# Windows_Hello_DIAL_HUB.net
KiCad netlist of a schematic drawn in EasyEDA Pro
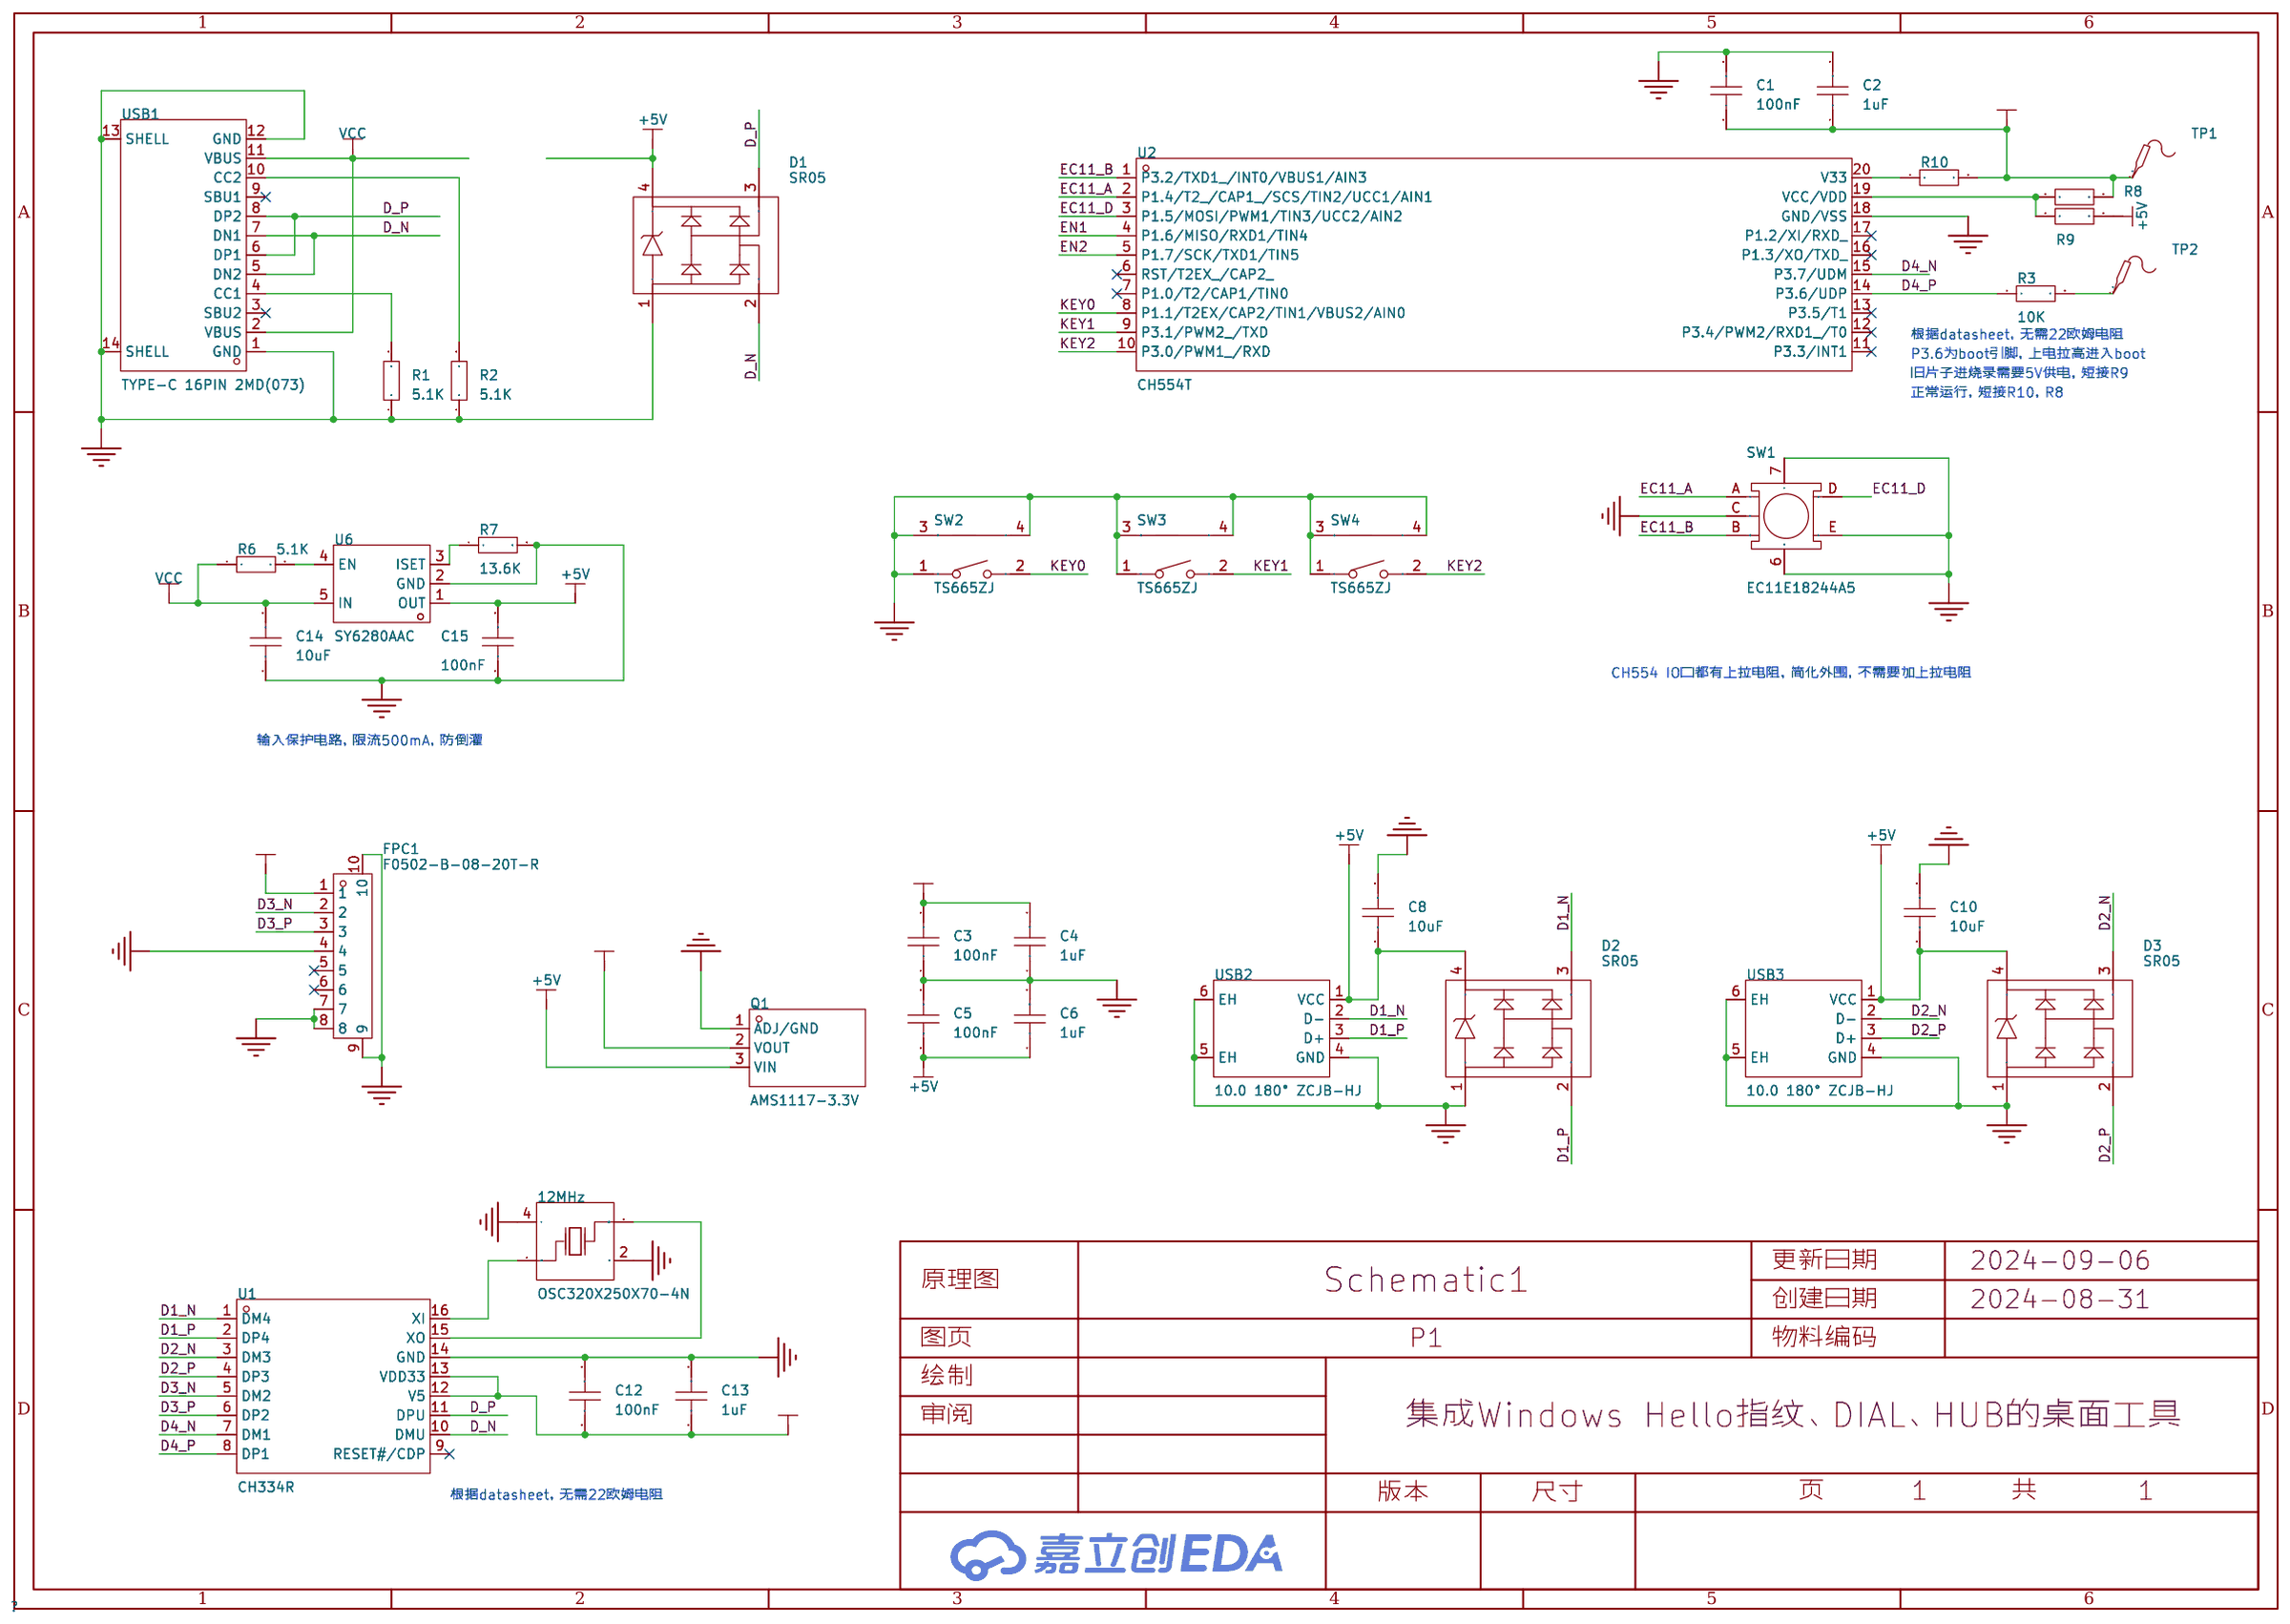
[diagram p0: schematic sheet]

(export (version "E")
  (design (tool "Eeschema 10.0.6"))
  (components
    (comp (ref "12MHz")
      (value "OSC320X250X70-4N")
      (footprint "easyedapro:CRYSTAL-SMD_4P-L3.2-W2.5-BL")
      (libsource (lib "easyedapro") (part "OSC320X250X70-4N"))
    )
    (comp (ref "C1")
      (value "100nF")
      (footprint "easyedapro:C0603")
      (libsource (lib "easyedapro") (part "CapAcitance"))
    )
    (comp (ref "C2")
      (value "1uF")
      (footprint "easyedapro:C0603")
      (libsource (lib "easyedapro") (part "CapAcitance"))
    )
    (comp (ref "C3")
      (value "100nF")
      (footprint "easyedapro:C0603")
      (libsource (lib "easyedapro") (part "CapAcitance"))
    )
    (comp (ref "C4")
      (value "1uF")
      (footprint "easyedapro:C0603")
      (libsource (lib "easyedapro") (part "CapAcitance"))
    )
    (comp (ref "C5")
      (value "100nF")
      (footprint "easyedapro:C0603")
      (libsource (lib "easyedapro") (part "CapAcitance"))
    )
    (comp (ref "C6")
      (value "1uF")
      (footprint "easyedapro:C0603")
      (libsource (lib "easyedapro") (part "CapAcitance"))
    )
    (comp (ref "C8")
      (value "10uF")
      (footprint "easyedapro:C0603")
      (libsource (lib "easyedapro") (part "CapAcitance"))
    )
    (comp (ref "C10")
      (value "10uF")
      (footprint "easyedapro:C0603")
      (libsource (lib "easyedapro") (part "CapAcitance"))
    )
    (comp (ref "C12")
      (value "100nF")
      (footprint "easyedapro:C0603")
      (libsource (lib "easyedapro") (part "CapAcitance"))
    )
    (comp (ref "C13")
      (value "1uF")
      (footprint "easyedapro:C0603")
      (libsource (lib "easyedapro") (part "CapAcitance"))
    )
    (comp (ref "C14")
      (value "10uF")
      (footprint "easyedapro:C0603")
      (libsource (lib "easyedapro") (part "CapAcitance"))
    )
    (comp (ref "C15")
      (value "100nF")
      (footprint "easyedapro:C0603")
      (libsource (lib "easyedapro") (part "CapAcitance"))
    )
    (comp (ref "D1")
      (value "SR05")
      (footprint "easyedapro:SOT-143-4_L2.9-W1.3-P1.90-LS2.4-BL")
      (fields (field (name "Manufacturer") "SEMBO(深波)"))
      (libsource (lib "easyedapro") (part "SR05_C782796"))
    )
    (comp (ref "D2")
      (value "SR05")
      (footprint "easyedapro:SOT-143-4_L2.9-W1.3-P1.90-LS2.4-BL")
      (fields (field (name "Manufacturer") "SEMBO(深波)"))
      (libsource (lib "easyedapro") (part "SR05_C782796"))
    )
    (comp (ref "D3")
      (value "SR05")
      (footprint "easyedapro:SOT-143-4_L2.9-W1.3-P1.90-LS2.4-BL")
      (fields (field (name "Manufacturer") "SEMBO(深波)"))
      (libsource (lib "easyedapro") (part "SR05_C782796"))
    )
    (comp (ref "FPC1")
      (value "F0502-B-08-20T-R")
      (footprint "easyedapro:FPC-SMD_F0502-B-08-20T-R")
      (description "锁定特性:翻盖式;触点类型:下接;触点数量:8P;间距:0.5mm;安装类型:卧贴;")
      (fields (field (name "Manufacturer") "XFCN(兴飞)"))
      (libsource (lib "easyedapro") (part "F0502-B-08-20T-R"))
    )
    (comp (ref "Q1")
      (value "AMS1117-3.3V")
      (footprint "easyedapro:SOT-89-3_L4.5-W2.5-P1.50-LS4.2-BR")
      (description "输出类型:固定;最大输入电压:18V;输出电压:3.3V;最大输出电流:1A;输出极性:正极;")
      (fields (field (name "Manufacturer") "MSKSEMI(美森科)"))
      (libsource (lib "easyedapro") (part "AMS1117-3.3V_C5120796"))
    )
    (comp (ref "R1") (value "5.1K") (footprint "easyedapro:R0402") (libsource (lib "easyedapro") (part "电阻")))
    (comp (ref "R2") (value "5.1K") (footprint "easyedapro:R0402") (libsource (lib "easyedapro") (part "电阻")))
    (comp (ref "R3") (value "10K") (footprint "easyedapro:R0402") (libsource (lib "easyedapro") (part "电阻")))
    (comp (ref "R6") (value "5.1K") (footprint "easyedapro:R0402") (libsource (lib "easyedapro") (part "电阻")))
    (comp (ref "R7")
      (value "13.6K")
      (footprint "easyedapro:R0402")
      (libsource (lib "easyedapro") (part "电阻"))
    )
    (comp (ref "R8") (value "10K") (footprint "easyedapro:R0402") (libsource (lib "easyedapro") (part "电阻")))
    (comp (ref "R9") (value "10K") (footprint "easyedapro:R0402") (libsource (lib "easyedapro") (part "电阻")))
    (comp (ref "R10") (value "10K") (footprint "easyedapro:R0402") (libsource (lib "easyedapro") (part "电阻")))
    (comp (ref "SW1")
      (value "EC11E18244A5")
      (footprint "easyedapro:SW-TH_EC11E18244A5")
      (fields (field (name "Manufacturer") "ALPSALPINE(阿尔卑斯阿尔派)"))
      (libsource (lib "easyedapro") (part "EC11E18244A5"))
    )
    (comp (ref "SW2")
      (value "TS665ZJ")
      (footprint "easyedapro:SW-TH_TS665ZJ")
      (fields (field (name "Manufacturer") "SHOU HAN(首韩)"))
      (libsource (lib "easyedapro") (part "TS665ZJ"))
    )
    (comp (ref "SW3")
      (value "TS665ZJ")
      (footprint "easyedapro:SW-TH_TS665ZJ")
      (fields (field (name "Manufacturer") "SHOU HAN(首韩)"))
      (libsource (lib "easyedapro") (part "TS665ZJ"))
    )
    (comp (ref "SW4")
      (value "TS665ZJ")
      (footprint "easyedapro:SW-TH_TS665ZJ")
      (fields (field (name "Manufacturer") "SHOU HAN(首韩)"))
      (libsource (lib "easyedapro") (part "TS665ZJ"))
    )
    (comp (ref "TP1")
      (value "~")
      (footprint "easyedapro:Test-Point-0.5mm")
      (description "Test Point 测试点")
      (libsource (lib "easyedapro") (part "Test-Point"))
    )
    (comp (ref "TP2")
      (value "~")
      (footprint "easyedapro:Test-Point-0.5mm")
      (description "Test Point 测试点")
      (libsource (lib "easyedapro") (part "Test-Point"))
    )
    (comp (ref "U1")
      (value "CH334R")
      (footprint "easyedapro:QSOP-16_L4.9-W3.9-P0.64-LS6.0-BL")
      (fields (field (name "Manufacturer") "WCH(南京沁恒)"))
      (libsource (lib "easyedapro") (part "CH334R"))
    )
    (comp (ref "U2")
      (value "CH554T")
      (footprint "easyedapro:TSSOP-20_L6.5-W4.4-P0.65-LS6.4-TL")
      (fields (field (name "Manufacturer") "WCH(南京沁恒)"))
      (libsource (lib "easyedapro") (part "CH554T_C2928938"))
    )
    (comp (ref "U6")
      (value "SY6280AAC")
      (footprint "easyedapro:SOT-23-5_L3.0-W1.7-P0.95-LS2.8-BL")
      (description "低能耗配电开关")
      (fields (field (name "Manufacturer") "silergy(矽力杰)"))
      (libsource (lib "easyedapro") (part "SY6280AAC"))
    )
    (comp (ref "USB1")
      (value "TYPE-C 16PIN 2MD(073)")
      (footprint "easyedapro:USB-C-SMD_TYPE-C-6PIN-2MD-073")
      (description "连接器类型:Type-C;标准:-;公母:母;端口数量:1;触点数量:16P;安装方式:卧贴;额定电流 - 电源:5A;工作温度范围:-25°C~+85°C;")
      (fields (field (name "Manufacturer") "SHOU HAN(首韩)"))
      (libsource (lib "easyedapro") (part "TYPE-C 16PIN 2MD(073)"))
    )
    (comp (ref "USB2")
      (value "10.0 180° ZCJB-HJ")
      (footprint "easyedapro:USB-A-TH_ZCJB-HJ")
      (description "连接器类型:Type-A;标准:USB 2.0;公母:母;端口数量:1;触点数量:4P;安装方式:直插;额定电流 - 电源:1.5A;工作温度范围:-25°C~+85°C;")
      (fields (field (name "Manufacturer") "SHOU HAN(首韩)"))
      (libsource (lib "easyedapro") (part "10.0 180° ZCJB-HJ"))
    )
    (comp (ref "USB3")
      (value "10.0 180° ZCJB-HJ")
      (footprint "easyedapro:USB-A-TH_ZCJB-HJ")
      (description "连接器类型:Type-A;标准:USB 2.0;公母:母;端口数量:1;触点数量:4P;安装方式:直插;额定电流 - 电源:1.5A;工作温度范围:-25°C~+85°C;")
      (fields (field (name "Manufacturer") "SHOU HAN(首韩)"))
      (libsource (lib "easyedapro") (part "10.0 180° ZCJB-HJ"))
    )
  )
  (nets
    (net (code "1") (name "+3.3V") (class "Default")
      (node (ref "C1") (pin "1") (pinfunction "1_1") (pintype "input"))
      (node (ref "C12") (pin "1") (pinfunction "1_1") (pintype "input"))
      (node (ref "C13") (pin "1") (pinfunction "1_1") (pintype "input"))
      (node (ref "C2") (pin "1") (pinfunction "1_1") (pintype "input"))
      (node (ref "C3") (pin "2") (pinfunction "2_2") (pintype "input"))
      (node (ref "C4") (pin "2") (pinfunction "2_2") (pintype "input"))
      (node (ref "FPC1") (pin "1") (pinfunction "1_1") (pintype "unspecified"))
      (node (ref "Q1") (pin "2") (pinfunction "VOUT_2") (pintype "unspecified"))
      (node (ref "R10") (pin "2") (pinfunction "2_2") (pintype "input"))
      (node (ref "R8") (pin "2") (pinfunction "2_2") (pintype "input"))
      (node (ref "TP1") (pin "1") (pinfunction "1_1") (pintype "input"))
      (node (ref "U1") (pin "12") (pinfunction "V5_12") (pintype "unspecified"))
      (node (ref "U1") (pin "13") (pinfunction "VDD33_13") (pintype "unspecified"))
    )
    (net (code "2") (name "+5V") (class "Default")
      (node (ref "C10") (pin "1") (pinfunction "1_1") (pintype "input"))
      (node (ref "C15") (pin "2") (pinfunction "2_2") (pintype "input"))
      (node (ref "C5") (pin "1") (pinfunction "1_1") (pintype "input"))
      (node (ref "C6") (pin "1") (pinfunction "1_1") (pintype "input"))
      (node (ref "C8") (pin "1") (pinfunction "1_1") (pintype "input"))
      (node (ref "D1") (pin "4") (pinfunction "4_4") (pintype "unspecified"))
      (node (ref "D2") (pin "4") (pinfunction "4_4") (pintype "unspecified"))
      (node (ref "D3") (pin "4") (pinfunction "4_4") (pintype "unspecified"))
      (node (ref "Q1") (pin "3") (pinfunction "VIN_3") (pintype "unspecified"))
      (node (ref "R9") (pin "2") (pinfunction "2_2") (pintype "input"))
      (node (ref "U6") (pin "1") (pinfunction "OUT_1") (pintype "unspecified"))
      (node (ref "USB2") (pin "1") (pinfunction "VCC_1") (pintype "input"))
      (node (ref "USB3") (pin "1") (pinfunction "VCC_1") (pintype "input"))
    )
    (net (code "3") (name "/D1_N") (class "Default")
      (node (ref "D2") (pin "3") (pinfunction "3_3") (pintype "unspecified"))
      (node (ref "U1") (pin "1") (pinfunction "DM4_1") (pintype "unspecified"))
      (node (ref "USB2") (pin "2") (pinfunction "D-_2") (pintype "input"))
    )
    (net (code "4") (name "/D1_P") (class "Default")
      (node (ref "D2") (pin "2") (pinfunction "2_2") (pintype "unspecified"))
      (node (ref "U1") (pin "2") (pinfunction "DP4_2") (pintype "unspecified"))
      (node (ref "USB2") (pin "3") (pinfunction "D+_3") (pintype "input"))
    )
    (net (code "5") (name "/D2_N") (class "Default")
      (node (ref "D3") (pin "3") (pinfunction "3_3") (pintype "unspecified"))
      (node (ref "U1") (pin "3") (pinfunction "DM3_3") (pintype "unspecified"))
      (node (ref "USB3") (pin "2") (pinfunction "D-_2") (pintype "input"))
    )
    (net (code "6") (name "/D2_P") (class "Default")
      (node (ref "D3") (pin "2") (pinfunction "2_2") (pintype "unspecified"))
      (node (ref "U1") (pin "4") (pinfunction "DP3_4") (pintype "unspecified"))
      (node (ref "USB3") (pin "3") (pinfunction "D+_3") (pintype "input"))
    )
    (net (code "7") (name "/D3_N") (class "Default")
      (node (ref "FPC1") (pin "2") (pinfunction "2_2") (pintype "unspecified"))
      (node (ref "U1") (pin "5") (pinfunction "DM2_5") (pintype "unspecified"))
    )
    (net (code "8") (name "/D3_P") (class "Default")
      (node (ref "FPC1") (pin "3") (pinfunction "3_3") (pintype "unspecified"))
      (node (ref "U1") (pin "6") (pinfunction "DP2_6") (pintype "unspecified"))
    )
    (net (code "9") (name "/D4_N") (class "Default")
      (node (ref "U1") (pin "7") (pinfunction "DM1_7") (pintype "unspecified"))
      (node (ref "U2") (pin "15") (pinfunction "P3.7/UDM_15") (pintype "unspecified"))
    )
    (net (code "10") (name "/D4_P") (class "Default")
      (node (ref "R3") (pin "1") (pinfunction "1_1") (pintype "input"))
      (node (ref "U1") (pin "8") (pinfunction "DP1_8") (pintype "unspecified"))
      (node (ref "U2") (pin "14") (pinfunction "P3.6/UDP_14") (pintype "unspecified"))
    )
    (net (code "11") (name "/D_N") (class "Default")
      (node (ref "D1") (pin "2") (pinfunction "2_2") (pintype "unspecified"))
      (node (ref "U1") (pin "10") (pinfunction "DMU_10") (pintype "unspecified"))
      (node (ref "USB1") (pin "5") (pinfunction "DN2_5") (pintype "unspecified"))
      (node (ref "USB1") (pin "7") (pinfunction "DN1_7") (pintype "unspecified"))
    )
    (net (code "12") (name "/D_P") (class "Default")
      (node (ref "D1") (pin "3") (pinfunction "3_3") (pintype "unspecified"))
      (node (ref "U1") (pin "11") (pinfunction "DPU_11") (pintype "unspecified"))
      (node (ref "USB1") (pin "6") (pinfunction "DP1_6") (pintype "unspecified"))
      (node (ref "USB1") (pin "8") (pinfunction "DP2_8") (pintype "unspecified"))
    )
    (net (code "13") (name "/EC11_A") (class "Default")
      (node (ref "SW1") (pin "A") (pinfunction "A_A") (pintype "unspecified"))
      (node (ref "U2") (pin "2") (pinfunction "P1.4/T2_/CAP1_/SCS/TIN2/UCC1/AIN1_2") (pintype "unspecified"))
    )
    (net (code "14") (name "/EC11_B") (class "Default")
      (node (ref "SW1") (pin "B") (pinfunction "B_B") (pintype "unspecified"))
      (node (ref "U2") (pin "1") (pinfunction "P3.2/TXD1_/INT0/VBUS1/AIN3_1") (pintype "unspecified"))
    )
    (net (code "15") (name "/EC11_D") (class "Default")
      (node (ref "SW1") (pin "D") (pinfunction "D_D") (pintype "unspecified"))
      (node (ref "U2") (pin "3") (pinfunction "P1.5/MOSI/PWM1/TIN3/UCC2/AIN2_3") (pintype "unspecified"))
    )
    (net (code "16") (name "/EN1") (class "Default")
      (node (ref "U2") (pin "4") (pinfunction "P1.6/MISO/RXD1/TIN4_4") (pintype "unspecified"))
    )
    (net (code "17") (name "/EN2") (class "Default")
      (node (ref "U2") (pin "5") (pinfunction "P1.7/SCK/TXD1/TIN5_5") (pintype "unspecified"))
    )
    (net (code "18") (name "/KEY0") (class "Default")
      (node (ref "SW2") (pin "2") (pinfunction "2_2") (pintype "input"))
      (node (ref "U2") (pin "8") (pinfunction "P1.1/T2EX/CAP2/TIN1/VBUS2/AIN0_8") (pintype "unspecified"))
    )
    (net (code "19") (name "/KEY1") (class "Default")
      (node (ref "SW3") (pin "2") (pinfunction "2_2") (pintype "input"))
      (node (ref "U2") (pin "9") (pinfunction "P3.1/PWM2_/TXD_9") (pintype "unspecified"))
    )
    (net (code "20") (name "/KEY2") (class "Default")
      (node (ref "SW4") (pin "2") (pinfunction "2_2") (pintype "input"))
      (node (ref "U2") (pin "10") (pinfunction "P3.0/PWM1_/RXD_10") (pintype "unspecified"))
    )
    (net (code "21") (name "GND") (class "Default")
      (node (ref "12MHz") (pin "2") (pinfunction "2_2") (pintype "input"))
      (node (ref "12MHz") (pin "4") (pinfunction "4_4") (pintype "input"))
      (node (ref "C1") (pin "2") (pinfunction "2_2") (pintype "input"))
      (node (ref "C10") (pin "2") (pinfunction "2_2") (pintype "input"))
      (node (ref "C12") (pin "2") (pinfunction "2_2") (pintype "input"))
      (node (ref "C13") (pin "2") (pinfunction "2_2") (pintype "input"))
      (node (ref "C14") (pin "1") (pinfunction "1_1") (pintype "input"))
      (node (ref "C15") (pin "1") (pinfunction "1_1") (pintype "input"))
      (node (ref "C2") (pin "2") (pinfunction "2_2") (pintype "input"))
      (node (ref "C3") (pin "1") (pinfunction "1_1") (pintype "input"))
      (node (ref "C4") (pin "1") (pinfunction "1_1") (pintype "input"))
      (node (ref "C5") (pin "2") (pinfunction "2_2") (pintype "input"))
      (node (ref "C6") (pin "2") (pinfunction "2_2") (pintype "input"))
      (node (ref "C8") (pin "2") (pinfunction "2_2") (pintype "input"))
      (node (ref "D1") (pin "1") (pinfunction "1_1") (pintype "unspecified"))
      (node (ref "D2") (pin "1") (pinfunction "1_1") (pintype "unspecified"))
      (node (ref "D3") (pin "1") (pinfunction "1_1") (pintype "unspecified"))
      (node (ref "FPC1") (pin "10") (pinfunction "10_10") (pintype "unspecified"))
      (node (ref "FPC1") (pin "4") (pinfunction "4_4") (pintype "unspecified"))
      (node (ref "FPC1") (pin "7") (pinfunction "7_7") (pintype "unspecified"))
      (node (ref "FPC1") (pin "8") (pinfunction "8_8") (pintype "unspecified"))
      (node (ref "FPC1") (pin "9") (pinfunction "9_9") (pintype "unspecified"))
      (node (ref "Q1") (pin "1") (pinfunction "ADJ/GND_1") (pintype "unspecified"))
      (node (ref "R1") (pin "1") (pinfunction "1_1") (pintype "input"))
      (node (ref "R2") (pin "1") (pinfunction "1_1") (pintype "input"))
      (node (ref "R7") (pin "2") (pinfunction "2_2") (pintype "input"))
      (node (ref "SW1") (pin "6") (pinfunction "6_6") (pintype "unspecified"))
      (node (ref "SW1") (pin "7") (pinfunction "7_7") (pintype "unspecified"))
      (node (ref "SW1") (pin "C") (pinfunction "C_C") (pintype "unspecified"))
      (node (ref "SW1") (pin "E") (pinfunction "E_E") (pintype "unspecified"))
      (node (ref "SW2") (pin "1") (pinfunction "1_1") (pintype "input"))
      (node (ref "SW2") (pin "3") (pinfunction "3_3") (pintype "input"))
      (node (ref "SW2") (pin "4") (pinfunction "4_4") (pintype "input"))
      (node (ref "SW3") (pin "1") (pinfunction "1_1") (pintype "input"))
      (node (ref "SW3") (pin "3") (pinfunction "3_3") (pintype "input"))
      (node (ref "SW3") (pin "4") (pinfunction "4_4") (pintype "input"))
      (node (ref "SW4") (pin "1") (pinfunction "1_1") (pintype "input"))
      (node (ref "SW4") (pin "3") (pinfunction "3_3") (pintype "input"))
      (node (ref "SW4") (pin "4") (pinfunction "4_4") (pintype "input"))
      (node (ref "U1") (pin "14") (pinfunction "GND_14") (pintype "unspecified"))
      (node (ref "U2") (pin "18") (pinfunction "GND/VSS_18") (pintype "unspecified"))
      (node (ref "U6") (pin "2") (pinfunction "GND_2") (pintype "unspecified"))
      (node (ref "USB1") (pin "1") (pinfunction "GND_1") (pintype "unspecified"))
      (node (ref "USB1") (pin "12") (pinfunction "GND_12") (pintype "unspecified"))
      (node (ref "USB1") (pin "13") (pinfunction "SHELL_13") (pintype "unspecified"))
      (node (ref "USB1") (pin "14") (pinfunction "SHELL_14") (pintype "unspecified"))
      (node (ref "USB2") (pin "4") (pinfunction "GND_4") (pintype "input"))
      (node (ref "USB2") (pin "5") (pinfunction "EH_5") (pintype "unspecified"))
      (node (ref "USB2") (pin "6") (pinfunction "EH_6") (pintype "unspecified"))
      (node (ref "USB3") (pin "4") (pinfunction "GND_4") (pintype "input"))
      (node (ref "USB3") (pin "5") (pinfunction "EH_5") (pintype "unspecified"))
      (node (ref "USB3") (pin "6") (pinfunction "EH_6") (pintype "unspecified"))
    )
    (net (code "22") (name "Net-(12MHz-OSC1)") (class "Default")
      (node (ref "12MHz") (pin "1") (pinfunction "OSC1_1") (pintype "input"))
      (node (ref "U1") (pin "16") (pinfunction "XI_16") (pintype "unspecified"))
    )
    (net (code "23") (name "Net-(12MHz-OSC2)") (class "Default")
      (node (ref "12MHz") (pin "3") (pinfunction "OSC2_3") (pintype "input"))
      (node (ref "U1") (pin "15") (pinfunction "XO_15") (pintype "unspecified"))
    )
    (net (code "24") (name "Net-(R3-Pad2)") (class "Default")
      (node (ref "R3") (pin "2") (pinfunction "2_2") (pintype "input"))
      (node (ref "TP2") (pin "1") (pinfunction "1_1") (pintype "input"))
    )
    (net (code "25") (name "Net-(U2-V33)") (class "Default")
      (node (ref "R10") (pin "1") (pinfunction "1_1") (pintype "input"))
      (node (ref "U2") (pin "20") (pinfunction "V33_20") (pintype "unspecified"))
    )
    (net (code "26") (name "Net-(U2-VCC{slash}VDD)") (class "Default")
      (node (ref "R8") (pin "1") (pinfunction "1_1") (pintype "input"))
      (node (ref "R9") (pin "1") (pinfunction "1_1") (pintype "input"))
      (node (ref "U2") (pin "19") (pinfunction "VCC/VDD_19") (pintype "unspecified"))
    )
    (net (code "27") (name "Net-(U6-EN)") (class "Default")
      (node (ref "R6") (pin "2") (pinfunction "2_2") (pintype "input"))
      (node (ref "U6") (pin "4") (pinfunction "EN_4") (pintype "unspecified"))
    )
    (net (code "28") (name "Net-(U6-ISET)") (class "Default")
      (node (ref "R7") (pin "1") (pinfunction "1_1") (pintype "input"))
      (node (ref "U6") (pin "3") (pinfunction "ISET_3") (pintype "unspecified"))
    )
    (net (code "29") (name "Net-(USB1-CC1)") (class "Default")
      (node (ref "R1") (pin "2") (pinfunction "2_2") (pintype "input"))
      (node (ref "USB1") (pin "4") (pinfunction "CC1_4") (pintype "unspecified"))
    )
    (net (code "30") (name "Net-(USB1-CC2)") (class "Default")
      (node (ref "R2") (pin "2") (pinfunction "2_2") (pintype "input"))
      (node (ref "USB1") (pin "10") (pinfunction "CC2_10") (pintype "unspecified"))
    )
    (net (code "31") (name "VCC") (class "Default")
      (node (ref "C14") (pin "2") (pinfunction "2_2") (pintype "input"))
      (node (ref "R6") (pin "1") (pinfunction "1_1") (pintype "input"))
      (node (ref "U6") (pin "5") (pinfunction "IN_5") (pintype "unspecified"))
      (node (ref "USB1") (pin "11") (pinfunction "VBUS_11") (pintype "unspecified"))
      (node (ref "USB1") (pin "2") (pinfunction "VBUS_2") (pintype "unspecified"))
    )
    (net (code "32") (name "unconnected-(FPC1-Pad5)") (class "Default")
      (node (ref "FPC1") (pin "5") (pinfunction "5_5") (pintype "unspecified+no_connect"))
    )
    (net (code "33") (name "unconnected-(FPC1-Pad6)") (class "Default")
      (node (ref "FPC1") (pin "6") (pinfunction "6_6") (pintype "unspecified+no_connect"))
    )
    (net (code "34") (name "unconnected-(U1-RESET#{slash}CDP-Pad9)") (class "Default")
      (node (ref "U1") (pin "9") (pinfunction "RESET#/CDP_9") (pintype "unspecified+no_connect"))
    )
    (net (code "35") (name "unconnected-(U2-P1.0{slash}T2{slash}CAP1{slash}TIN0-Pad7)") (class "Default")
      (node (ref "U2") (pin "7") (pinfunction "P1.0/T2/CAP1/TIN0_7") (pintype "unspecified+no_connect"))
    )
    (net (code "36") (name "unconnected-(U2-P1.2{slash}XI{slash}RXD_-Pad17)") (class "Default")
      (node (ref "U2") (pin "17") (pinfunction "P1.2/XI/RXD__17") (pintype "unspecified+no_connect"))
    )
    (net (code "37") (name "unconnected-(U2-P1.3{slash}XO{slash}TXD_-Pad16)") (class "Default")
      (node (ref "U2") (pin "16") (pinfunction "P1.3/XO/TXD__16") (pintype "unspecified+no_connect"))
    )
    (net (code "38") (name "unconnected-(U2-P3.3{slash}INT1-Pad11)") (class "Default")
      (node (ref "U2") (pin "11") (pinfunction "P3.3/INT1_11") (pintype "unspecified+no_connect"))
    )
    (net (code "39") (name "unconnected-(U2-P3.4{slash}PWM2{slash}RXD1_{slash}T0-Pad12)") (class "Default")
      (node (ref "U2") (pin "12") (pinfunction "P3.4/PWM2/RXD1_/T0_12") (pintype "unspecified+no_connect"))
    )
    (net (code "40") (name "unconnected-(U2-P3.5{slash}T1-Pad13)") (class "Default")
      (node (ref "U2") (pin "13") (pinfunction "P3.5/T1_13") (pintype "unspecified+no_connect"))
    )
    (net (code "41") (name "unconnected-(U2-RST{slash}T2EX_{slash}CAP2_-Pad6)") (class "Default")
      (node (ref "U2") (pin "6") (pinfunction "RST/T2EX_/CAP2__6") (pintype "unspecified+no_connect"))
    )
    (net (code "42") (name "unconnected-(USB1-SBU1-Pad9)") (class "Default")
      (node (ref "USB1") (pin "9") (pinfunction "SBU1_9") (pintype "unspecified+no_connect"))
    )
    (net (code "43") (name "unconnected-(USB1-SBU2-Pad3)") (class "Default")
      (node (ref "USB1") (pin "3") (pinfunction "SBU2_3") (pintype "unspecified+no_connect"))
    )
  )
)
